# Mosfet_and_Driver.net
KiCad netlist of a schematic drawn in Altium Designer
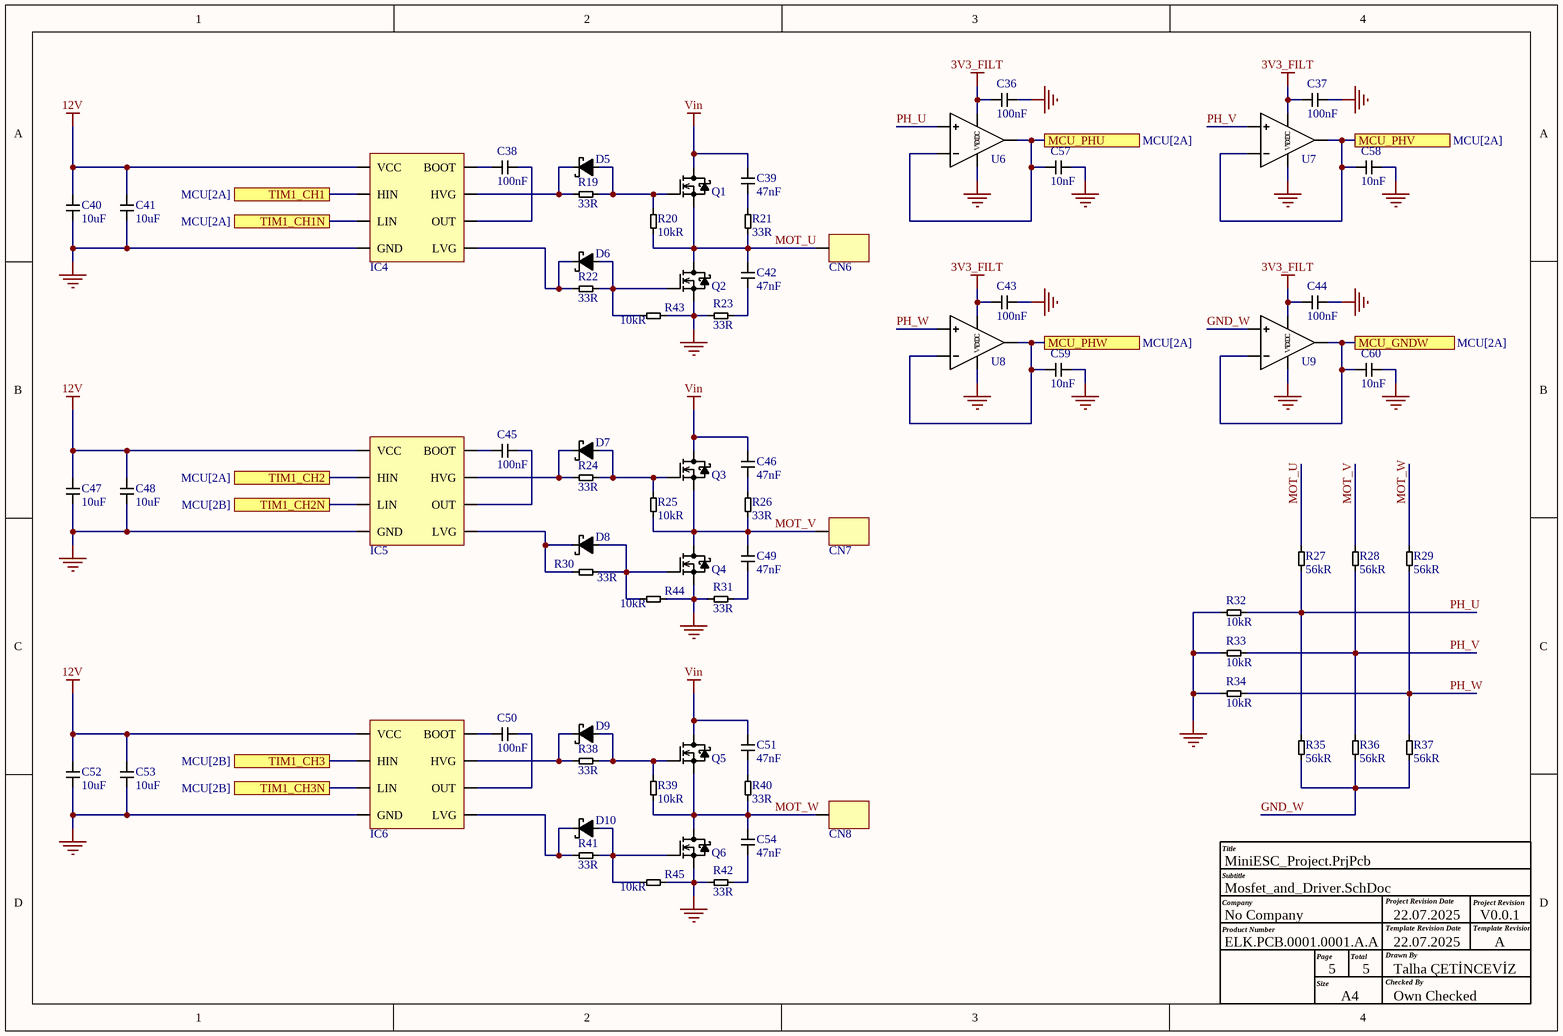
[diagram p0: Mosfet_and_Driver.SchDoc]

(export (version "E")
  (design (tool "Eeschema 10.0.6"))
  (components
    (comp (ref "C36")
      (value "100nF")
      (footprint "CAP 0603")
      (description "Multilayer Ceramic Capacitor, CC Series, 0.1 - F, - 10%, X7R, 50 V, 0603 [1608 Metric]")
      (fields
        (field (name "MANUFACTURER") "Yageo")
        (field (name "MANUFACTURER PART NUMBER") "CC0603KRX7R9BB104")
      )
      (libsource (lib "ESC_Int") (part "CC0603KRX7R9BB104"))
    )
    (comp (ref "C37")
      (value "100nF")
      (footprint "CAP 0603")
      (description "Multilayer Ceramic Capacitor, CC Series, 0.1 - F, - 10%, X7R, 50 V, 0603 [1608 Metric]")
      (fields
        (field (name "MANUFACTURER") "Yageo")
        (field (name "MANUFACTURER PART NUMBER") "CC0603KRX7R9BB104")
      )
      (libsource (lib "ESC_Int") (part "CC0603KRX7R9BB104"))
    )
    (comp (ref "C38")
      (value "100nF")
      (footprint "CAP 0805")
      (description "50V 100nF X7R ±10% 0805 Multilayer Ceramic Capacitors MLCC - SMD/SMT ROHS")
      (fields
        (field (name "MANUFACTURER") "Samsung")
        (field (name "MANUFACTURER PART NUMBER") "CL21B104KBCNNNC")
      )
      (libsource (lib "ESC_Int") (part "CL21B104KBCNNNC"))
    )
    (comp (ref "C39")
      (value "47nF")
      (footprint "CAP 1206")
      (description "MLCC (3216) 1206 47nF 50VDC ±10% X7R")
      (fields
        (field (name "MANUFACTURER") "Samsung")
        (field (name "MANUFACTURER PART NUMBER") "CL31B473KBCNNNC")
      )
      (libsource (lib "ESC_Int") (part "CL31B473KBCNNNC"))
    )
    (comp (ref "C40")
      (value "10uF")
      (footprint "CAP 0805")
      (description "25V 10uF X5R ±10% 0805 Multilayer Ceramic Capacitors MLCC - SMD/SMT ROHS")
      (fields
        (field (name "MANUFACTURER") "Samsung")
        (field (name "MANUFACTURER PART NUMBER") "CL21A106KAYNNNE")
      )
      (libsource (lib "ESC_Int") (part "CL21A106KAYNNNE"))
    )
    (comp (ref "C41")
      (value "10uF")
      (footprint "CAP 0805")
      (description "25V 10uF X5R ±10% 0805 Multilayer Ceramic Capacitors MLCC - SMD/SMT ROHS")
      (fields
        (field (name "MANUFACTURER") "Samsung")
        (field (name "MANUFACTURER PART NUMBER") "CL21A106KAYNNNE")
      )
      (libsource (lib "ESC_Int") (part "CL21A106KAYNNNE"))
    )
    (comp (ref "C42")
      (value "47nF")
      (footprint "CAP 1206")
      (description "MLCC (3216) 1206 47nF 50VDC ±10% X7R")
      (fields
        (field (name "MANUFACTURER") "Samsung")
        (field (name "MANUFACTURER PART NUMBER") "CL31B473KBCNNNC")
      )
      (libsource (lib "ESC_Int") (part "CL31B473KBCNNNC"))
    )
    (comp (ref "C43")
      (value "100nF")
      (footprint "CAP 0603")
      (description "Multilayer Ceramic Capacitor, CC Series, 0.1 - F, - 10%, X7R, 50 V, 0603 [1608 Metric]")
      (fields
        (field (name "MANUFACTURER") "Yageo")
        (field (name "MANUFACTURER PART NUMBER") "CC0603KRX7R9BB104")
      )
      (libsource (lib "ESC_Int") (part "CC0603KRX7R9BB104"))
    )
    (comp (ref "C44")
      (value "100nF")
      (footprint "CAP 0603")
      (description "Multilayer Ceramic Capacitor, CC Series, 0.1 - F, - 10%, X7R, 50 V, 0603 [1608 Metric]")
      (fields
        (field (name "MANUFACTURER") "Yageo")
        (field (name "MANUFACTURER PART NUMBER") "CC0603KRX7R9BB104")
      )
      (libsource (lib "ESC_Int") (part "CC0603KRX7R9BB104"))
    )
    (comp (ref "C45")
      (value "100nF")
      (footprint "CAP 0805")
      (description "50V 100nF X7R ±10% 0805 Multilayer Ceramic Capacitors MLCC - SMD/SMT ROHS")
      (fields
        (field (name "MANUFACTURER") "Samsung")
        (field (name "MANUFACTURER PART NUMBER") "CL21B104KBCNNNC")
      )
      (libsource (lib "ESC_Int") (part "CL21B104KBCNNNC"))
    )
    (comp (ref "C46")
      (value "47nF")
      (footprint "CAP 1206")
      (description "MLCC (3216) 1206 47nF 50VDC ±10% X7R")
      (fields
        (field (name "MANUFACTURER") "Samsung")
        (field (name "MANUFACTURER PART NUMBER") "CL31B473KBCNNNC")
      )
      (libsource (lib "ESC_Int") (part "CL31B473KBCNNNC"))
    )
    (comp (ref "C47")
      (value "10uF")
      (footprint "CAP 0805")
      (description "25V 10uF X5R ±10% 0805 Multilayer Ceramic Capacitors MLCC - SMD/SMT ROHS")
      (fields
        (field (name "MANUFACTURER") "Samsung")
        (field (name "MANUFACTURER PART NUMBER") "CL21A106KAYNNNE")
      )
      (libsource (lib "ESC_Int") (part "CL21A106KAYNNNE"))
    )
    (comp (ref "C48")
      (value "10uF")
      (footprint "CAP 0805")
      (description "25V 10uF X5R ±10% 0805 Multilayer Ceramic Capacitors MLCC - SMD/SMT ROHS")
      (fields
        (field (name "MANUFACTURER") "Samsung")
        (field (name "MANUFACTURER PART NUMBER") "CL21A106KAYNNNE")
      )
      (libsource (lib "ESC_Int") (part "CL21A106KAYNNNE"))
    )
    (comp (ref "C49")
      (value "47nF")
      (footprint "CAP 1206")
      (description "MLCC (3216) 1206 47nF 50VDC ±10% X7R")
      (fields
        (field (name "MANUFACTURER") "Samsung")
        (field (name "MANUFACTURER PART NUMBER") "CL31B473KBCNNNC")
      )
      (libsource (lib "ESC_Int") (part "CL31B473KBCNNNC"))
    )
    (comp (ref "C50")
      (value "100nF")
      (footprint "CAP 0805")
      (description "50V 100nF X7R ±10% 0805 Multilayer Ceramic Capacitors MLCC - SMD/SMT ROHS")
      (fields
        (field (name "MANUFACTURER") "Samsung")
        (field (name "MANUFACTURER PART NUMBER") "CL21B104KBCNNNC")
      )
      (libsource (lib "ESC_Int") (part "CL21B104KBCNNNC"))
    )
    (comp (ref "C51")
      (value "47nF")
      (footprint "CAP 1206")
      (description "MLCC (3216) 1206 47nF 50VDC ±10% X7R")
      (fields
        (field (name "MANUFACTURER") "Samsung")
        (field (name "MANUFACTURER PART NUMBER") "CL31B473KBCNNNC")
      )
      (libsource (lib "ESC_Int") (part "CL31B473KBCNNNC"))
    )
    (comp (ref "C52")
      (value "10uF")
      (footprint "CAP 0805")
      (description "25V 10uF X5R ±10% 0805 Multilayer Ceramic Capacitors MLCC - SMD/SMT ROHS")
      (fields
        (field (name "MANUFACTURER") "Samsung")
        (field (name "MANUFACTURER PART NUMBER") "CL21A106KAYNNNE")
      )
      (libsource (lib "ESC_Int") (part "CL21A106KAYNNNE"))
    )
    (comp (ref "C53")
      (value "10uF")
      (footprint "CAP 0805")
      (description "25V 10uF X5R ±10% 0805 Multilayer Ceramic Capacitors MLCC - SMD/SMT ROHS")
      (fields
        (field (name "MANUFACTURER") "Samsung")
        (field (name "MANUFACTURER PART NUMBER") "CL21A106KAYNNNE")
      )
      (libsource (lib "ESC_Int") (part "CL21A106KAYNNNE"))
    )
    (comp (ref "C54")
      (value "47nF")
      (footprint "CAP 1206")
      (description "MLCC (3216) 1206 47nF 50VDC ±10% X7R")
      (fields
        (field (name "MANUFACTURER") "Samsung")
        (field (name "MANUFACTURER PART NUMBER") "CL31B473KBCNNNC")
      )
      (libsource (lib "ESC_Int") (part "CL31B473KBCNNNC"))
    )
    (comp (ref "C57")
      (value "10nF")
      (footprint "CAP 0603")
      (description "50V 10nF X7R ±10% 0603 Multilayer Ceramic Capacitors MLCC - SMD/SMT ROHS")
      (fields
        (field (name "MANUFACTURER") "Samsung")
        (field (name "MANUFACTURER PART NUMBER") "CL10B103KB8NNNC")
      )
      (libsource (lib "ESC_Int") (part "CL10B103KB8NNNC"))
    )
    (comp (ref "C58")
      (value "10nF")
      (footprint "CAP 0603")
      (description "50V 10nF X7R ±10% 0603 Multilayer Ceramic Capacitors MLCC - SMD/SMT ROHS")
      (fields
        (field (name "MANUFACTURER") "Samsung")
        (field (name "MANUFACTURER PART NUMBER") "CL10B103KB8NNNC")
      )
      (libsource (lib "ESC_Int") (part "CL10B103KB8NNNC"))
    )
    (comp (ref "C59")
      (value "10nF")
      (footprint "CAP 0603")
      (description "50V 10nF X7R ±10% 0603 Multilayer Ceramic Capacitors MLCC - SMD/SMT ROHS")
      (fields
        (field (name "MANUFACTURER") "Samsung")
        (field (name "MANUFACTURER PART NUMBER") "CL10B103KB8NNNC")
      )
      (libsource (lib "ESC_Int") (part "CL10B103KB8NNNC"))
    )
    (comp (ref "C60")
      (value "10nF")
      (footprint "CAP 0603")
      (description "50V 10nF X7R ±10% 0603 Multilayer Ceramic Capacitors MLCC - SMD/SMT ROHS")
      (fields
        (field (name "MANUFACTURER") "Samsung")
        (field (name "MANUFACTURER PART NUMBER") "CL10B103KB8NNNC")
      )
      (libsource (lib "ESC_Int") (part "CL10B103KB8NNNC"))
    )
    (comp (ref "CN6")
      (value "SMD PAD 1")
      (footprint "SMD PAD 1")
      (libsource (lib "ESC_Int") (part "SMD PAD 1"))
    )
    (comp (ref "CN7")
      (value "SMD PAD 1")
      (footprint "SMD PAD 1")
      (libsource (lib "ESC_Int") (part "SMD PAD 1"))
    )
    (comp (ref "CN8")
      (value "SMD PAD 1")
      (footprint "SMD PAD 1")
      (libsource (lib "ESC_Int") (part "SMD PAD 1"))
    )
    (comp (ref "D5")
      (value "SS2060FL_R1_00001")
      (footprint "SOD123-FL")
      (description "Schottky-diode 2A 60V SOD123FL")
      (fields (field (name "MANUFACTURER") "Pan Jit"))
      (libsource (lib "ESC_Int") (part "SS2060FL_R1_00001"))
    )
    (comp (ref "D6")
      (value "SS2060FL_R1_00001")
      (footprint "SOD123-FL")
      (description "Schottky-diode 2A 60V SOD123FL")
      (fields (field (name "MANUFACTURER") "Pan Jit"))
      (libsource (lib "ESC_Int") (part "SS2060FL_R1_00001"))
    )
    (comp (ref "D7")
      (value "SS2060FL_R1_00001")
      (footprint "SOD123-FL")
      (description "Schottky-diode 2A 60V SOD123FL")
      (fields (field (name "MANUFACTURER") "Pan Jit"))
      (libsource (lib "ESC_Int") (part "SS2060FL_R1_00001"))
    )
    (comp (ref "D8")
      (value "SS2060FL_R1_00001")
      (footprint "SOD123-FL")
      (description "Schottky-diode 2A 60V SOD123FL")
      (fields (field (name "MANUFACTURER") "Pan Jit"))
      (libsource (lib "ESC_Int") (part "SS2060FL_R1_00001"))
    )
    (comp (ref "D9")
      (value "SS2060FL_R1_00001")
      (footprint "SOD123-FL")
      (description "Schottky-diode 2A 60V SOD123FL")
      (fields (field (name "MANUFACTURER") "Pan Jit"))
      (libsource (lib "ESC_Int") (part "SS2060FL_R1_00001"))
    )
    (comp (ref "D10")
      (value "SS2060FL_R1_00001")
      (footprint "SOD123-FL")
      (description "Schottky-diode 2A 60V SOD123FL")
      (fields (field (name "MANUFACTURER") "Pan Jit"))
      (libsource (lib "ESC_Int") (part "SS2060FL_R1_00001"))
    )
    (comp (ref "IC4")
      (value "L6388ED013TR")
      (footprint "SOIC-8")
      (description "L6388E Series 17 V 650 mA High Voltage High and Low-Side Driver - SOIC-8")
      (fields (field (name "MANUFACTURER") "STMicroelectronics"))
      (libsource (lib "ESC_Int") (part "L6388ED013TR"))
    )
    (comp (ref "IC5")
      (value "L6388ED013TR")
      (footprint "SOIC-8")
      (description "L6388E Series 17 V 650 mA High Voltage High and Low-Side Driver - SOIC-8")
      (fields (field (name "MANUFACTURER") "STMicroelectronics"))
      (libsource (lib "ESC_Int") (part "L6388ED013TR"))
    )
    (comp (ref "IC6")
      (value "L6388ED013TR")
      (footprint "SOIC-8")
      (description "L6388E Series 17 V 650 mA High Voltage High and Low-Side Driver - SOIC-8")
      (fields (field (name "MANUFACTURER") "STMicroelectronics"))
      (libsource (lib "ESC_Int") (part "L6388ED013TR"))
    )
    (comp (ref "Q1")
      (value "P80FH5ENK-7071")
      (footprint "D2PAK-3")
      (description "MOSFET POWER 80A 50V N-CH TO263AB")
      (fields (field (name "MANUFACTURER") "SHINDENGEN"))
      (libsource (lib "ESC_Int") (part "P80FH5ENK-7071"))
    )
    (comp (ref "Q2")
      (value "P80FH5ENK-7071")
      (footprint "D2PAK-3")
      (description "MOSFET POWER 80A 50V N-CH TO263AB")
      (fields (field (name "MANUFACTURER") "SHINDENGEN"))
      (libsource (lib "ESC_Int") (part "P80FH5ENK-7071"))
    )
    (comp (ref "Q3")
      (value "P80FH5ENK-7071")
      (footprint "D2PAK-3")
      (description "MOSFET POWER 80A 50V N-CH TO263AB")
      (fields (field (name "MANUFACTURER") "SHINDENGEN"))
      (libsource (lib "ESC_Int") (part "P80FH5ENK-7071"))
    )
    (comp (ref "Q4")
      (value "P80FH5ENK-7071")
      (footprint "D2PAK-3")
      (description "MOSFET POWER 80A 50V N-CH TO263AB")
      (fields (field (name "MANUFACTURER") "SHINDENGEN"))
      (libsource (lib "ESC_Int") (part "P80FH5ENK-7071"))
    )
    (comp (ref "Q5")
      (value "P80FH5ENK-7071")
      (footprint "D2PAK-3")
      (description "MOSFET POWER 80A 50V N-CH TO263AB")
      (fields (field (name "MANUFACTURER") "SHINDENGEN"))
      (libsource (lib "ESC_Int") (part "P80FH5ENK-7071"))
    )
    (comp (ref "Q6")
      (value "P80FH5ENK-7071")
      (footprint "D2PAK-3")
      (description "MOSFET POWER 80A 50V N-CH TO263AB")
      (fields (field (name "MANUFACTURER") "SHINDENGEN"))
      (libsource (lib "ESC_Int") (part "P80FH5ENK-7071"))
    )
    (comp (ref "R19")
      (value "33R")
      (footprint "RES 0805")
      (description "Res General Purpose Thick Film 0805 33 Ohm 1% 1/8W ±200ppm/°C Molded T/R")
      (fields
        (field (name "MANUFACTURER") "Multicomp")
        (field (name "MANUFACTURER PART NUMBER") "MC0805S8F330JT5E")
      )
      (libsource (lib "ESC_Int") (part "0805S8F330JT5E"))
    )
    (comp (ref "R20")
      (value "10kR")
      (footprint "RES 0603")
      (description "SMD Chip Resistor, 10 Kohm, ½ 1%, 100 Mw, 0603 [1608 Metric], Thick Film, General Purpose")
      (fields
        (field (name "MANUFACTURER") "Yageo")
        (field (name "MANUFACTURER PART NUMBER") "RC0603FR-0710KL")
      )
      (libsource (lib "ESC_Int") (part "RC0603FR-0710KL"))
    )
    (comp (ref "R21")
      (value "33R")
      (footprint "RES 1206")
      (description "RES.(3216) 1206 33 Ohms 1% 1/4W-S AUTOMOTIV")
      (fields
        (field (name "MANUFACTURER") "Royal Electronic Factory")
        (field (name "MANUFACTURER PART NUMBER") "CQ06S4F330JT5E")
      )
      (libsource (lib "ESC_Int") (part "CQ06S4F330JT5E"))
    )
    (comp (ref "R22")
      (value "33R")
      (footprint "RES 0805")
      (description "Res General Purpose Thick Film 0805 33 Ohm 1% 1/8W ±200ppm/°C Molded T/R")
      (fields
        (field (name "MANUFACTURER") "Multicomp")
        (field (name "MANUFACTURER PART NUMBER") "MC0805S8F330JT5E")
      )
      (libsource (lib "ESC_Int") (part "0805S8F330JT5E"))
    )
    (comp (ref "R23")
      (value "33R")
      (footprint "RES 1206")
      (description "RES.(3216) 1206 33 Ohms 1% 1/4W-S AUTOMOTIV")
      (fields
        (field (name "MANUFACTURER") "Royal Electronic Factory")
        (field (name "MANUFACTURER PART NUMBER") "CQ06S4F330JT5E")
      )
      (libsource (lib "ESC_Int") (part "CQ06S4F330JT5E"))
    )
    (comp (ref "R24")
      (value "33R")
      (footprint "RES 0805")
      (description "Res General Purpose Thick Film 0805 33 Ohm 1% 1/8W ±200ppm/°C Molded T/R")
      (fields
        (field (name "MANUFACTURER") "Multicomp")
        (field (name "MANUFACTURER PART NUMBER") "MC0805S8F330JT5E")
      )
      (libsource (lib "ESC_Int") (part "0805S8F330JT5E"))
    )
    (comp (ref "R25")
      (value "10kR")
      (footprint "RES 0603")
      (description "SMD Chip Resistor, 10 Kohm, ½ 1%, 100 Mw, 0603 [1608 Metric], Thick Film, General Purpose")
      (fields
        (field (name "MANUFACTURER") "Yageo")
        (field (name "MANUFACTURER PART NUMBER") "RC0603FR-0710KL")
      )
      (libsource (lib "ESC_Int") (part "RC0603FR-0710KL"))
    )
    (comp (ref "R26")
      (value "33R")
      (footprint "RES 1206")
      (description "RES.(3216) 1206 33 Ohms 1% 1/4W-S AUTOMOTIV")
      (fields
        (field (name "MANUFACTURER") "Royal Electronic Factory")
        (field (name "MANUFACTURER PART NUMBER") "CQ06S4F330JT5E")
      )
      (libsource (lib "ESC_Int") (part "CQ06S4F330JT5E"))
    )
    (comp (ref "R27")
      (value "56kR")
      (footprint "RES 0603")
      (description "Res Thick Film 0603 56K Ohm 1% 0.1W(1/10W) ±100ppm/C Pad SMD T/R")
      (fields
        (field (name "MANUFACTURER") "Royal Electronic Factory")
        (field (name "MANUFACTURER PART NUMBER") "0603SAF5602T5E")
      )
      (libsource (lib "ESC_Int") (part "0603SAF5602T5E"))
    )
    (comp (ref "R28")
      (value "56kR")
      (footprint "RES 0603")
      (description "Res Thick Film 0603 56K Ohm 1% 0.1W(1/10W) ±100ppm/C Pad SMD T/R")
      (fields
        (field (name "MANUFACTURER") "Royal Electronic Factory")
        (field (name "MANUFACTURER PART NUMBER") "0603SAF5602T5E")
      )
      (libsource (lib "ESC_Int") (part "0603SAF5602T5E"))
    )
    (comp (ref "R29")
      (value "56kR")
      (footprint "RES 0603")
      (description "Res Thick Film 0603 56K Ohm 1% 0.1W(1/10W) ±100ppm/C Pad SMD T/R")
      (fields
        (field (name "MANUFACTURER") "Royal Electronic Factory")
        (field (name "MANUFACTURER PART NUMBER") "0603SAF5602T5E")
      )
      (libsource (lib "ESC_Int") (part "0603SAF5602T5E"))
    )
    (comp (ref "R30")
      (value "33R")
      (footprint "RES 0805")
      (description "Res General Purpose Thick Film 0805 33 Ohm 1% 1/8W ±200ppm/°C Molded T/R")
      (fields
        (field (name "MANUFACTURER") "Multicomp")
        (field (name "MANUFACTURER PART NUMBER") "MC0805S8F330JT5E")
      )
      (libsource (lib "ESC_Int") (part "0805S8F330JT5E"))
    )
    (comp (ref "R31")
      (value "33R")
      (footprint "RES 1206")
      (description "RES.(3216) 1206 33 Ohms 1% 1/4W-S AUTOMOTIV")
      (fields
        (field (name "MANUFACTURER") "Royal Electronic Factory")
        (field (name "MANUFACTURER PART NUMBER") "CQ06S4F330JT5E")
      )
      (libsource (lib "ESC_Int") (part "CQ06S4F330JT5E"))
    )
    (comp (ref "R32")
      (value "10kR")
      (footprint "RES 0603")
      (description "SMD Chip Resistor, 10 Kohm, ½ 1%, 100 Mw, 0603 [1608 Metric], Thick Film, General Purpose")
      (fields
        (field (name "MANUFACTURER") "Yageo")
        (field (name "MANUFACTURER PART NUMBER") "RC0603FR-0710KL")
      )
      (libsource (lib "ESC_Int") (part "RC0603FR-0710KL"))
    )
    (comp (ref "R33")
      (value "10kR")
      (footprint "RES 0603")
      (description "SMD Chip Resistor, 10 Kohm, ½ 1%, 100 Mw, 0603 [1608 Metric], Thick Film, General Purpose")
      (fields
        (field (name "MANUFACTURER") "Yageo")
        (field (name "MANUFACTURER PART NUMBER") "RC0603FR-0710KL")
      )
      (libsource (lib "ESC_Int") (part "RC0603FR-0710KL"))
    )
    (comp (ref "R34")
      (value "10kR")
      (footprint "RES 0603")
      (description "SMD Chip Resistor, 10 Kohm, ½ 1%, 100 Mw, 0603 [1608 Metric], Thick Film, General Purpose")
      (fields
        (field (name "MANUFACTURER") "Yageo")
        (field (name "MANUFACTURER PART NUMBER") "RC0603FR-0710KL")
      )
      (libsource (lib "ESC_Int") (part "RC0603FR-0710KL"))
    )
    (comp (ref "R35")
      (value "56kR")
      (footprint "RES 0603")
      (description "Res Thick Film 0603 56K Ohm 1% 0.1W(1/10W) ±100ppm/C Pad SMD T/R")
      (fields
        (field (name "MANUFACTURER") "Royal Electronic Factory")
        (field (name "MANUFACTURER PART NUMBER") "0603SAF5602T5E")
      )
      (libsource (lib "ESC_Int") (part "0603SAF5602T5E"))
    )
    (comp (ref "R36")
      (value "56kR")
      (footprint "RES 0603")
      (description "Res Thick Film 0603 56K Ohm 1% 0.1W(1/10W) ±100ppm/C Pad SMD T/R")
      (fields
        (field (name "MANUFACTURER") "Royal Electronic Factory")
        (field (name "MANUFACTURER PART NUMBER") "0603SAF5602T5E")
      )
      (libsource (lib "ESC_Int") (part "0603SAF5602T5E"))
    )
    (comp (ref "R37")
      (value "56kR")
      (footprint "RES 0603")
      (description "Res Thick Film 0603 56K Ohm 1% 0.1W(1/10W) ±100ppm/C Pad SMD T/R")
      (fields
        (field (name "MANUFACTURER") "Royal Electronic Factory")
        (field (name "MANUFACTURER PART NUMBER") "0603SAF5602T5E")
      )
      (libsource (lib "ESC_Int") (part "0603SAF5602T5E"))
    )
    (comp (ref "R38")
      (value "33R")
      (footprint "RES 0805")
      (description "Res General Purpose Thick Film 0805 33 Ohm 1% 1/8W ±200ppm/°C Molded T/R")
      (fields
        (field (name "MANUFACTURER") "Multicomp")
        (field (name "MANUFACTURER PART NUMBER") "MC0805S8F330JT5E")
      )
      (libsource (lib "ESC_Int") (part "0805S8F330JT5E"))
    )
    (comp (ref "R39")
      (value "10kR")
      (footprint "RES 0603")
      (description "SMD Chip Resistor, 10 Kohm, ½ 1%, 100 Mw, 0603 [1608 Metric], Thick Film, General Purpose")
      (fields
        (field (name "MANUFACTURER") "Yageo")
        (field (name "MANUFACTURER PART NUMBER") "RC0603FR-0710KL")
      )
      (libsource (lib "ESC_Int") (part "RC0603FR-0710KL"))
    )
    (comp (ref "R40")
      (value "33R")
      (footprint "RES 1206")
      (description "RES.(3216) 1206 33 Ohms 1% 1/4W-S AUTOMOTIV")
      (fields
        (field (name "MANUFACTURER") "Royal Electronic Factory")
        (field (name "MANUFACTURER PART NUMBER") "CQ06S4F330JT5E")
      )
      (libsource (lib "ESC_Int") (part "CQ06S4F330JT5E"))
    )
    (comp (ref "R41")
      (value "33R")
      (footprint "RES 0805")
      (description "Res General Purpose Thick Film 0805 33 Ohm 1% 1/8W ±200ppm/°C Molded T/R")
      (fields
        (field (name "MANUFACTURER") "Multicomp")
        (field (name "MANUFACTURER PART NUMBER") "MC0805S8F330JT5E")
      )
      (libsource (lib "ESC_Int") (part "0805S8F330JT5E"))
    )
    (comp (ref "R42")
      (value "33R")
      (footprint "RES 1206")
      (description "RES.(3216) 1206 33 Ohms 1% 1/4W-S AUTOMOTIV")
      (fields
        (field (name "MANUFACTURER") "Royal Electronic Factory")
        (field (name "MANUFACTURER PART NUMBER") "CQ06S4F330JT5E")
      )
      (libsource (lib "ESC_Int") (part "CQ06S4F330JT5E"))
    )
    (comp (ref "R43")
      (value "10kR")
      (footprint "RES 0603")
      (description "SMD Chip Resistor, 10 Kohm, ½ 1%, 100 Mw, 0603 [1608 Metric], Thick Film, General Purpose")
      (fields
        (field (name "MANUFACTURER") "Yageo")
        (field (name "MANUFACTURER PART NUMBER") "RC0603FR-0710KL")
      )
      (libsource (lib "ESC_Int") (part "RC0603FR-0710KL"))
    )
    (comp (ref "R44")
      (value "10kR")
      (footprint "RES 0603")
      (description "SMD Chip Resistor, 10 Kohm, ½ 1%, 100 Mw, 0603 [1608 Metric], Thick Film, General Purpose")
      (fields
        (field (name "MANUFACTURER") "Yageo")
        (field (name "MANUFACTURER PART NUMBER") "RC0603FR-0710KL")
      )
      (libsource (lib "ESC_Int") (part "RC0603FR-0710KL"))
    )
    (comp (ref "R45")
      (value "10kR")
      (footprint "RES 0603")
      (description "SMD Chip Resistor, 10 Kohm, ½ 1%, 100 Mw, 0603 [1608 Metric], Thick Film, General Purpose")
      (fields
        (field (name "MANUFACTURER") "Yageo")
        (field (name "MANUFACTURER PART NUMBER") "RC0603FR-0710KL")
      )
      (libsource (lib "ESC_Int") (part "RC0603FR-0710KL"))
    )
    (comp (ref "U6")
      (value "LMV321ILT")
      (footprint "SOT23-5")
      (description "LMV321 Series 6 V 1 MHz Low Power Rail to Rail Operational Amplifier - SOT-23-5")
      (fields (field (name "MANUFACTURER") "STMicroelectronics"))
      (libsource (lib "ESC_Int") (part "LMV321ILT"))
    )
    (comp (ref "U7")
      (value "LMV321ILT")
      (footprint "SOT23-5")
      (description "LMV321 Series 6 V 1 MHz Low Power Rail to Rail Operational Amplifier - SOT-23-5")
      (fields (field (name "MANUFACTURER") "STMicroelectronics"))
      (libsource (lib "ESC_Int") (part "LMV321ILT"))
    )
    (comp (ref "U8")
      (value "LMV321ILT")
      (footprint "SOT23-5")
      (description "LMV321 Series 6 V 1 MHz Low Power Rail to Rail Operational Amplifier - SOT-23-5")
      (fields (field (name "MANUFACTURER") "STMicroelectronics"))
      (libsource (lib "ESC_Int") (part "LMV321ILT"))
    )
    (comp (ref "U9")
      (value "LMV321ILT")
      (footprint "SOT23-5")
      (description "LMV321 Series 6 V 1 MHz Low Power Rail to Rail Operational Amplifier - SOT-23-5")
      (fields (field (name "MANUFACTURER") "STMicroelectronics"))
      (libsource (lib "ESC_Int") (part "LMV321ILT"))
    )
  )
  (nets
    (net (code "1") (name "/GND_W") (class "Default")
      (node (ref "R35") (pin "1") (pinfunction "1_1") (pintype "passive"))
      (node (ref "R36") (pin "1") (pinfunction "1_1") (pintype "passive"))
      (node (ref "R37") (pin "1") (pinfunction "1_1") (pintype "passive"))
      (node (ref "U9") (pin "1") (pinfunction "NON_Inverting_input_1") (pintype "passive"))
    )
    (net (code "2") (name "/MCU_GNDW") (class "Default")
      (node (ref "C60") (pin "1") (pinfunction "1_1") (pintype "passive"))
      (node (ref "U9") (pin "3") (pinfunction "Inverting_Input_3") (pintype "passive"))
      (node (ref "U9") (pin "4") (pinfunction "Output_4") (pintype "passive"))
    )
    (net (code "3") (name "/MCU_PHU") (class "Default")
      (node (ref "C57") (pin "1") (pinfunction "1_1") (pintype "passive"))
      (node (ref "U6") (pin "3") (pinfunction "Inverting_Input_3") (pintype "passive"))
      (node (ref "U6") (pin "4") (pinfunction "Output_4") (pintype "passive"))
    )
    (net (code "4") (name "/MCU_PHV") (class "Default")
      (node (ref "C58") (pin "1") (pinfunction "1_1") (pintype "passive"))
      (node (ref "U7") (pin "3") (pinfunction "Inverting_Input_3") (pintype "passive"))
      (node (ref "U7") (pin "4") (pinfunction "Output_4") (pintype "passive"))
    )
    (net (code "5") (name "/MCU_PHW") (class "Default")
      (node (ref "C59") (pin "1") (pinfunction "1_1") (pintype "passive"))
      (node (ref "U8") (pin "3") (pinfunction "Inverting_Input_3") (pintype "passive"))
      (node (ref "U8") (pin "4") (pinfunction "Output_4") (pintype "passive"))
    )
    (net (code "6") (name "/MOT_U") (class "Default")
      (node (ref "C42") (pin "2") (pinfunction "2_2") (pintype "passive"))
      (node (ref "CN6") (pin "1") (pinfunction "1_1") (pintype "passive"))
      (node (ref "Q1") (pin "3") (pinfunction "Source_3") (pintype "passive"))
      (node (ref "Q2") (pin "2") (pinfunction "Drain_2") (pintype "passive"))
      (node (ref "R20") (pin "1") (pinfunction "1_1") (pintype "passive"))
      (node (ref "R21") (pin "1") (pinfunction "1_1") (pintype "passive"))
      (node (ref "R27") (pin "2") (pinfunction "2_2") (pintype "passive"))
    )
    (net (code "7") (name "/MOT_V") (class "Default")
      (node (ref "C49") (pin "2") (pinfunction "2_2") (pintype "passive"))
      (node (ref "CN7") (pin "1") (pinfunction "1_1") (pintype "passive"))
      (node (ref "Q3") (pin "3") (pinfunction "Source_3") (pintype "passive"))
      (node (ref "Q4") (pin "2") (pinfunction "Drain_2") (pintype "passive"))
      (node (ref "R25") (pin "1") (pinfunction "1_1") (pintype "passive"))
      (node (ref "R26") (pin "1") (pinfunction "1_1") (pintype "passive"))
      (node (ref "R28") (pin "2") (pinfunction "2_2") (pintype "passive"))
    )
    (net (code "8") (name "/MOT_W") (class "Default")
      (node (ref "C54") (pin "2") (pinfunction "2_2") (pintype "passive"))
      (node (ref "CN8") (pin "1") (pinfunction "1_1") (pintype "passive"))
      (node (ref "Q5") (pin "3") (pinfunction "Source_3") (pintype "passive"))
      (node (ref "Q6") (pin "2") (pinfunction "Drain_2") (pintype "passive"))
      (node (ref "R29") (pin "2") (pinfunction "2_2") (pintype "passive"))
      (node (ref "R39") (pin "1") (pinfunction "1_1") (pintype "passive"))
      (node (ref "R40") (pin "1") (pinfunction "1_1") (pintype "passive"))
    )
    (net (code "9") (name "/PH_U") (class "Default")
      (node (ref "R27") (pin "1") (pinfunction "1_1") (pintype "passive"))
      (node (ref "R32") (pin "1") (pinfunction "1_1") (pintype "passive"))
      (node (ref "R35") (pin "2") (pinfunction "2_2") (pintype "passive"))
      (node (ref "U6") (pin "1") (pinfunction "NON_Inverting_input_1") (pintype "passive"))
    )
    (net (code "10") (name "/PH_V") (class "Default")
      (node (ref "R28") (pin "1") (pinfunction "1_1") (pintype "passive"))
      (node (ref "R33") (pin "1") (pinfunction "1_1") (pintype "passive"))
      (node (ref "R36") (pin "2") (pinfunction "2_2") (pintype "passive"))
      (node (ref "U7") (pin "1") (pinfunction "NON_Inverting_input_1") (pintype "passive"))
    )
    (net (code "11") (name "/PH_W") (class "Default")
      (node (ref "R29") (pin "1") (pinfunction "1_1") (pintype "passive"))
      (node (ref "R34") (pin "1") (pinfunction "1_1") (pintype "passive"))
      (node (ref "R37") (pin "2") (pinfunction "2_2") (pintype "passive"))
      (node (ref "U8") (pin "1") (pinfunction "NON_Inverting_input_1") (pintype "passive"))
    )
    (net (code "12") (name "/TIM1_CH1") (class "Default")
      (node (ref "IC4") (pin "2") (pinfunction "HIN_2") (pintype "passive"))
    )
    (net (code "13") (name "/TIM1_CH1N") (class "Default")
      (node (ref "IC4") (pin "1") (pinfunction "LIN_1") (pintype "passive"))
    )
    (net (code "14") (name "/TIM1_CH2") (class "Default")
      (node (ref "IC5") (pin "2") (pinfunction "HIN_2") (pintype "passive"))
    )
    (net (code "15") (name "/TIM1_CH2N") (class "Default")
      (node (ref "IC5") (pin "1") (pinfunction "LIN_1") (pintype "passive"))
    )
    (net (code "16") (name "/TIM1_CH3") (class "Default")
      (node (ref "IC6") (pin "2") (pinfunction "HIN_2") (pintype "passive"))
    )
    (net (code "17") (name "/TIM1_CH3N") (class "Default")
      (node (ref "IC6") (pin "1") (pinfunction "LIN_1") (pintype "passive"))
    )
    (net (code "18") (name "3V3_FILT") (class "Default")
      (node (ref "C36") (pin "1") (pinfunction "1_1") (pintype "passive"))
      (node (ref "C37") (pin "1") (pinfunction "1_1") (pintype "passive"))
      (node (ref "C43") (pin "1") (pinfunction "1_1") (pintype "passive"))
      (node (ref "C44") (pin "1") (pinfunction "1_1") (pintype "passive"))
      (node (ref "U6") (pin "5") (pinfunction "VCC_5") (pintype "passive"))
      (node (ref "U7") (pin "5") (pinfunction "VCC_5") (pintype "passive"))
      (node (ref "U8") (pin "5") (pinfunction "VCC_5") (pintype "passive"))
      (node (ref "U9") (pin "5") (pinfunction "VCC_5") (pintype "passive"))
    )
    (net (code "19") (name "12V") (class "Default")
      (node (ref "C40") (pin "2") (pinfunction "2_2") (pintype "passive"))
      (node (ref "C41") (pin "2") (pinfunction "2_2") (pintype "passive"))
      (node (ref "C47") (pin "2") (pinfunction "2_2") (pintype "passive"))
      (node (ref "C48") (pin "2") (pinfunction "2_2") (pintype "passive"))
      (node (ref "C52") (pin "2") (pinfunction "2_2") (pintype "passive"))
      (node (ref "C53") (pin "2") (pinfunction "2_2") (pintype "passive"))
      (node (ref "IC4") (pin "3") (pinfunction "VCC_3") (pintype "passive"))
      (node (ref "IC5") (pin "3") (pinfunction "VCC_3") (pintype "passive"))
      (node (ref "IC6") (pin "3") (pinfunction "VCC_3") (pintype "passive"))
    )
    (net (code "20") (name "GND") (class "Default")
      (node (ref "C36") (pin "2") (pinfunction "2_2") (pintype "passive"))
      (node (ref "C37") (pin "2") (pinfunction "2_2") (pintype "passive"))
      (node (ref "C40") (pin "1") (pinfunction "3_1") (pintype "passive"))
      (node (ref "C41") (pin "1") (pinfunction "3_1") (pintype "passive"))
      (node (ref "C43") (pin "2") (pinfunction "2_2") (pintype "passive"))
      (node (ref "C44") (pin "2") (pinfunction "2_2") (pintype "passive"))
      (node (ref "C47") (pin "1") (pinfunction "3_1") (pintype "passive"))
      (node (ref "C48") (pin "1") (pinfunction "3_1") (pintype "passive"))
      (node (ref "C52") (pin "1") (pinfunction "3_1") (pintype "passive"))
      (node (ref "C53") (pin "1") (pinfunction "3_1") (pintype "passive"))
      (node (ref "C57") (pin "2") (pinfunction "2_2") (pintype "passive"))
      (node (ref "C58") (pin "2") (pinfunction "2_2") (pintype "passive"))
      (node (ref "C59") (pin "2") (pinfunction "2_2") (pintype "passive"))
      (node (ref "C60") (pin "2") (pinfunction "2_2") (pintype "passive"))
      (node (ref "IC4") (pin "4") (pinfunction "GND_4") (pintype "passive"))
      (node (ref "IC5") (pin "4") (pinfunction "GND_4") (pintype "passive"))
      (node (ref "IC6") (pin "4") (pinfunction "GND_4") (pintype "passive"))
      (node (ref "Q2") (pin "3") (pinfunction "Source_3") (pintype "passive"))
      (node (ref "Q4") (pin "3") (pinfunction "Source_3") (pintype "passive"))
      (node (ref "Q6") (pin "3") (pinfunction "Source_3") (pintype "passive"))
      (node (ref "R23") (pin "2") (pinfunction "2_2") (pintype "passive"))
      (node (ref "R31") (pin "2") (pinfunction "2_2") (pintype "passive"))
      (node (ref "R32") (pin "2") (pinfunction "2_2") (pintype "passive"))
      (node (ref "R33") (pin "2") (pinfunction "2_2") (pintype "passive"))
      (node (ref "R34") (pin "2") (pinfunction "2_2") (pintype "passive"))
      (node (ref "R42") (pin "2") (pinfunction "2_2") (pintype "passive"))
      (node (ref "R43") (pin "2") (pinfunction "2_2") (pintype "passive"))
      (node (ref "R44") (pin "2") (pinfunction "2_2") (pintype "passive"))
      (node (ref "R45") (pin "2") (pinfunction "2_2") (pintype "passive"))
      (node (ref "U6") (pin "2") (pinfunction "VDD_2") (pintype "passive"))
      (node (ref "U7") (pin "2") (pinfunction "VDD_2") (pintype "passive"))
      (node (ref "U8") (pin "2") (pinfunction "VDD_2") (pintype "passive"))
      (node (ref "U9") (pin "2") (pinfunction "VDD_2") (pintype "passive"))
    )
    (net (code "21") (name "Net-(C38-3)") (class "Default")
      (node (ref "C38") (pin "1") (pinfunction "3_1") (pintype "passive"))
      (node (ref "IC4") (pin "8") (pinfunction "BOOT_8") (pintype "passive"))
    )
    (net (code "22") (name "Net-(C39-3)") (class "Default")
      (node (ref "C39") (pin "1") (pinfunction "3_1") (pintype "passive"))
      (node (ref "R21") (pin "2") (pinfunction "2_2") (pintype "passive"))
    )
    (net (code "23") (name "Net-(C42-3)") (class "Default")
      (node (ref "C42") (pin "1") (pinfunction "3_1") (pintype "passive"))
      (node (ref "R23") (pin "1") (pinfunction "1_1") (pintype "passive"))
    )
    (net (code "24") (name "Net-(C45-3)") (class "Default")
      (node (ref "C45") (pin "1") (pinfunction "3_1") (pintype "passive"))
      (node (ref "IC5") (pin "8") (pinfunction "BOOT_8") (pintype "passive"))
    )
    (net (code "25") (name "Net-(C46-3)") (class "Default")
      (node (ref "C46") (pin "1") (pinfunction "3_1") (pintype "passive"))
      (node (ref "R26") (pin "2") (pinfunction "2_2") (pintype "passive"))
    )
    (net (code "26") (name "Net-(C49-3)") (class "Default")
      (node (ref "C49") (pin "1") (pinfunction "3_1") (pintype "passive"))
      (node (ref "R31") (pin "1") (pinfunction "1_1") (pintype "passive"))
    )
    (net (code "27") (name "Net-(C50-3)") (class "Default")
      (node (ref "C50") (pin "1") (pinfunction "3_1") (pintype "passive"))
      (node (ref "IC6") (pin "8") (pinfunction "BOOT_8") (pintype "passive"))
    )
    (net (code "28") (name "Net-(C51-3)") (class "Default")
      (node (ref "C51") (pin "1") (pinfunction "3_1") (pintype "passive"))
      (node (ref "R40") (pin "2") (pinfunction "2_2") (pintype "passive"))
    )
    (net (code "29") (name "Net-(C54-3)") (class "Default")
      (node (ref "C54") (pin "1") (pinfunction "3_1") (pintype "passive"))
      (node (ref "R42") (pin "1") (pinfunction "1_1") (pintype "passive"))
    )
    (net (code "30") (name "Net-(IC4-HVG)") (class "Default")
      (node (ref "D5") (pin "C") (pinfunction "C_C") (pintype "passive"))
      (node (ref "IC4") (pin "7") (pinfunction "HVG_7") (pintype "passive"))
      (node (ref "R19") (pin "1") (pinfunction "1_1") (pintype "passive"))
    )
    (net (code "31") (name "Net-(IC4-LVG)") (class "Default")
      (node (ref "D6") (pin "C") (pinfunction "C_C") (pintype "passive"))
      (node (ref "IC4") (pin "5") (pinfunction "LVG_5") (pintype "passive"))
      (node (ref "R22") (pin "1") (pinfunction "1_1") (pintype "passive"))
    )
    (net (code "32") (name "Net-(IC4-OUT)") (class "Default")
      (node (ref "C38") (pin "2") (pinfunction "2_2") (pintype "passive"))
      (node (ref "IC4") (pin "6") (pinfunction "OUT_6") (pintype "passive"))
    )
    (net (code "33") (name "Net-(IC5-HVG)") (class "Default")
      (node (ref "D7") (pin "C") (pinfunction "C_C") (pintype "passive"))
      (node (ref "IC5") (pin "7") (pinfunction "HVG_7") (pintype "passive"))
      (node (ref "R24") (pin "1") (pinfunction "1_1") (pintype "passive"))
    )
    (net (code "34") (name "Net-(IC5-LVG)") (class "Default")
      (node (ref "D8") (pin "C") (pinfunction "C_C") (pintype "passive"))
      (node (ref "IC5") (pin "5") (pinfunction "LVG_5") (pintype "passive"))
      (node (ref "R30") (pin "1") (pinfunction "1_1") (pintype "passive"))
    )
    (net (code "35") (name "Net-(IC5-OUT)") (class "Default")
      (node (ref "C45") (pin "2") (pinfunction "2_2") (pintype "passive"))
      (node (ref "IC5") (pin "6") (pinfunction "OUT_6") (pintype "passive"))
    )
    (net (code "36") (name "Net-(IC6-HVG)") (class "Default")
      (node (ref "D9") (pin "C") (pinfunction "C_C") (pintype "passive"))
      (node (ref "IC6") (pin "7") (pinfunction "HVG_7") (pintype "passive"))
      (node (ref "R38") (pin "1") (pinfunction "1_1") (pintype "passive"))
    )
    (net (code "37") (name "Net-(IC6-LVG)") (class "Default")
      (node (ref "D10") (pin "C") (pinfunction "C_C") (pintype "passive"))
      (node (ref "IC6") (pin "5") (pinfunction "LVG_5") (pintype "passive"))
      (node (ref "R41") (pin "1") (pinfunction "1_1") (pintype "passive"))
    )
    (net (code "38") (name "Net-(IC6-OUT)") (class "Default")
      (node (ref "C50") (pin "2") (pinfunction "2_2") (pintype "passive"))
      (node (ref "IC6") (pin "6") (pinfunction "OUT_6") (pintype "passive"))
    )
    (net (code "39") (name "Net-(Q1-Gate)") (class "Default")
      (node (ref "D5") (pin "A") (pinfunction "A_A") (pintype "passive"))
      (node (ref "Q1") (pin "1") (pinfunction "Gate_1") (pintype "passive"))
      (node (ref "R19") (pin "2") (pinfunction "2_2") (pintype "passive"))
      (node (ref "R20") (pin "2") (pinfunction "2_2") (pintype "passive"))
    )
    (net (code "40") (name "Net-(Q2-Gate)") (class "Default")
      (node (ref "D6") (pin "A") (pinfunction "A_A") (pintype "passive"))
      (node (ref "Q2") (pin "1") (pinfunction "Gate_1") (pintype "passive"))
      (node (ref "R22") (pin "2") (pinfunction "2_2") (pintype "passive"))
      (node (ref "R43") (pin "1") (pinfunction "1_1") (pintype "passive"))
    )
    (net (code "41") (name "Net-(Q3-Gate)") (class "Default")
      (node (ref "D7") (pin "A") (pinfunction "A_A") (pintype "passive"))
      (node (ref "Q3") (pin "1") (pinfunction "Gate_1") (pintype "passive"))
      (node (ref "R24") (pin "2") (pinfunction "2_2") (pintype "passive"))
      (node (ref "R25") (pin "2") (pinfunction "2_2") (pintype "passive"))
    )
    (net (code "42") (name "Net-(Q4-Gate)") (class "Default")
      (node (ref "D8") (pin "A") (pinfunction "A_A") (pintype "passive"))
      (node (ref "Q4") (pin "1") (pinfunction "Gate_1") (pintype "passive"))
      (node (ref "R30") (pin "2") (pinfunction "2_2") (pintype "passive"))
      (node (ref "R44") (pin "1") (pinfunction "1_1") (pintype "passive"))
    )
    (net (code "43") (name "Net-(Q5-Gate)") (class "Default")
      (node (ref "D9") (pin "A") (pinfunction "A_A") (pintype "passive"))
      (node (ref "Q5") (pin "1") (pinfunction "Gate_1") (pintype "passive"))
      (node (ref "R38") (pin "2") (pinfunction "2_2") (pintype "passive"))
      (node (ref "R39") (pin "2") (pinfunction "2_2") (pintype "passive"))
    )
    (net (code "44") (name "Net-(Q6-Gate)") (class "Default")
      (node (ref "D10") (pin "A") (pinfunction "A_A") (pintype "passive"))
      (node (ref "Q6") (pin "1") (pinfunction "Gate_1") (pintype "passive"))
      (node (ref "R41") (pin "2") (pinfunction "2_2") (pintype "passive"))
      (node (ref "R45") (pin "1") (pinfunction "1_1") (pintype "passive"))
    )
    (net (code "45") (name "Vin") (class "Default")
      (node (ref "C39") (pin "2") (pinfunction "2_2") (pintype "passive"))
      (node (ref "C46") (pin "2") (pinfunction "2_2") (pintype "passive"))
      (node (ref "C51") (pin "2") (pinfunction "2_2") (pintype "passive"))
      (node (ref "Q1") (pin "2") (pinfunction "Drain_2") (pintype "passive"))
      (node (ref "Q3") (pin "2") (pinfunction "Drain_2") (pintype "passive"))
      (node (ref "Q5") (pin "2") (pinfunction "Drain_2") (pintype "passive"))
    )
  )
)
